# sensors_and_led.net
KiCad netlist of a schematic drawn in Altium Designer
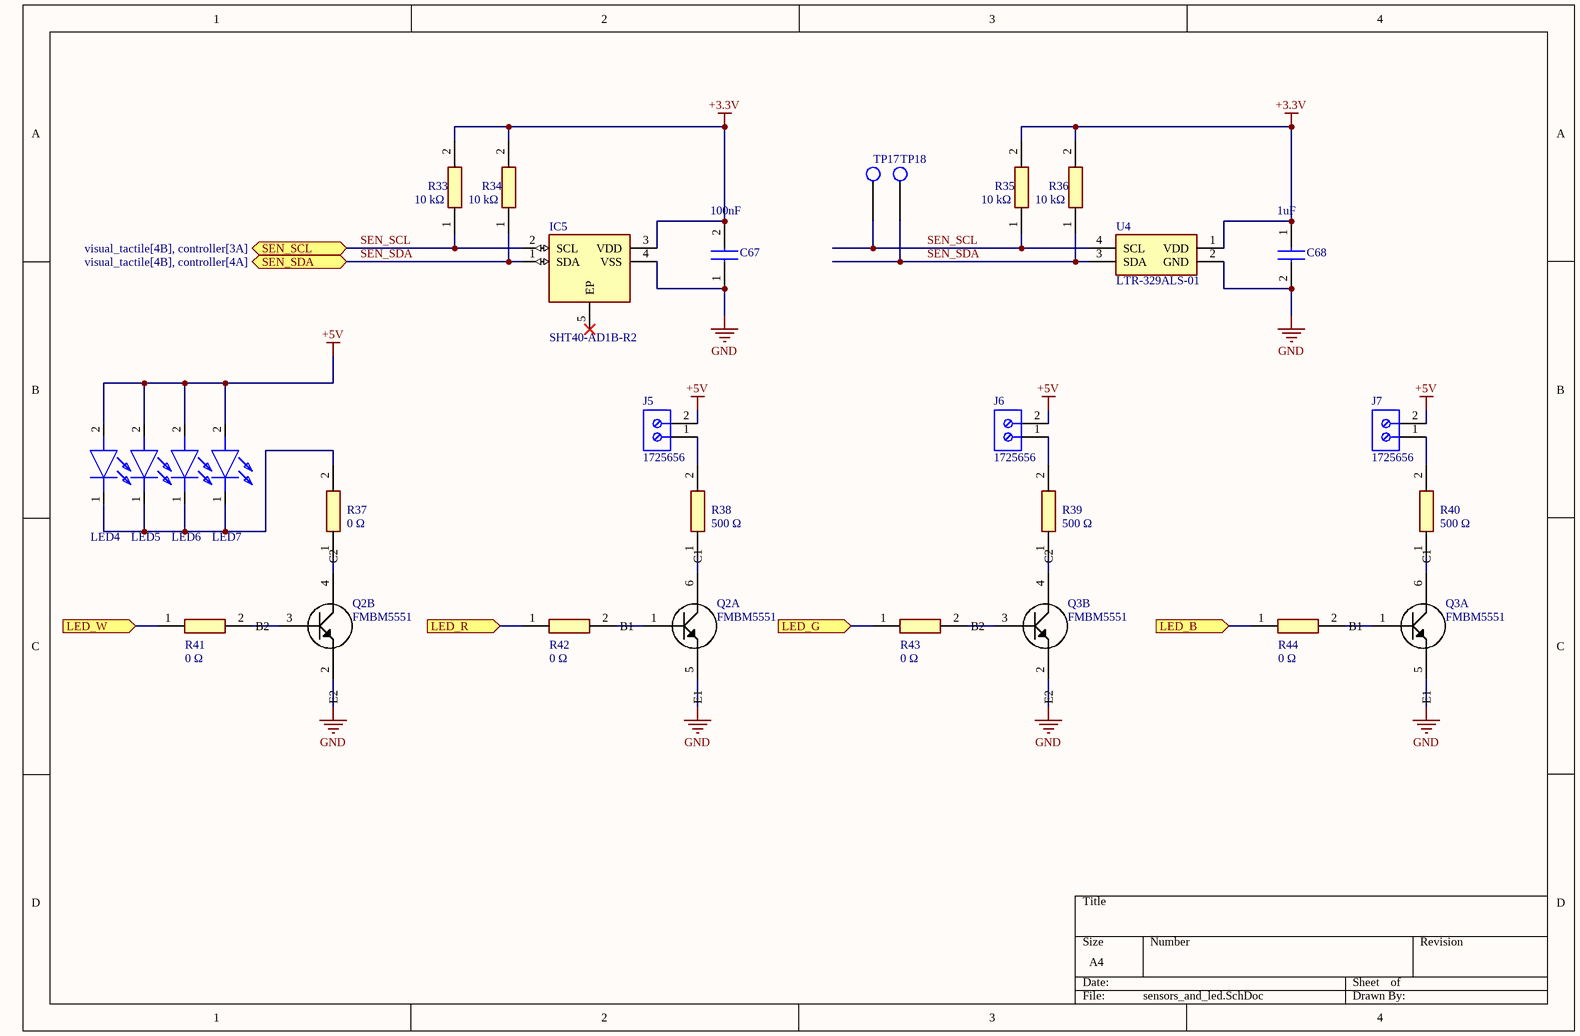
[diagram p0: sensors_and_led.SchDoc]

(export (version "E")
  (design (tool "Eeschema 10.0.6"))
  (components
    (comp (ref "C67")
      (value "100nF")
      (footprint "PCB_library:CAPC1608X87N")
      (fields
        (field (name "MANUFACTURER_PART_NUMBER") "C0603C300J5GACTU")
        (field (name "MOUSER PART NUMBER") "80-C0603C300J5G")
        (field (name "MANUFACTURER") "TDK")
      )
      (libsource (lib "PCB_library") (part "C0603C300J5GACTU"))
    )
    (comp (ref "C68")
      (value "1uF")
      (footprint "PCB_library:CAPC1608X87N")
      (fields
        (field (name "MANUFACTURER_PART_NUMBER") "C0603C300J5GACTU")
        (field (name "MOUSER PART NUMBER") "80-C0603C300J5G")
        (field (name "MANUFACTURER") "Kyocera AVX")
      )
      (libsource (lib "PCB_library") (part "C0603C300J5GACTU"))
    )
    (comp (ref "IC5")
      (value "SHT40-AD1B-R2")
      (footprint "PCB_library:SON80P150X150X59-5N")
      (description "Integrated Circuit")
      (fields (field (name "MOUSER PART NUMBER") "403-SHT40-AD1B-R2"))
      (libsource (lib "PCB_library") (part "SHT40-AD1B-R2"))
    )
    (comp (ref "J5")
      (value "1725656")
      (footprint "PHOE-1725656-2")
      (description "Male Header, Pitch 2.54 mm, 1 x 2 Position, Height 9 mm, Tail Length 3.5 mm")
      (fields (field (name "MANUFACTURER") "Phoenix Contact"))
      (libsource (lib "Altium Content Vault") (part "CN-1P-F-TB2"))
    )
    (comp (ref "J6")
      (value "1725656")
      (footprint "PHOE-1725656-2")
      (description "Male Header, Pitch 2.54 mm, 1 x 2 Position, Height 9 mm, Tail Length 3.5 mm")
      (fields (field (name "MANUFACTURER") "Phoenix Contact"))
      (libsource (lib "Altium Content Vault") (part "CN-1P-F-TB2"))
    )
    (comp (ref "J7")
      (value "1725656")
      (footprint "PHOE-1725656-2")
      (description "Male Header, Pitch 2.54 mm, 1 x 2 Position, Height 9 mm, Tail Length 3.5 mm")
      (fields (field (name "MANUFACTURER") "Phoenix Contact"))
      (libsource (lib "Altium Content Vault") (part "CN-1P-F-TB2"))
    )
    (comp (ref "LED4")
      (value "JE2835BWT-P-U30GA0000-N0000001")
      (footprint "PCB_library:JE2835BWTPU30GA0000N0000001")
      (description "LED")
      (fields
        (field (name "MANUFACTURER_PART_NUMBER") "JE2835BWT-P-U35GA0000-N0000001")
        (field (name "MOUSER PART NUMBER") "941-JE2835BWTPU30GAN")
      )
      (libsource (lib "PCB_library") (part "JE2835BWT-P-U30GA0000-N0000001"))
    )
    (comp (ref "LED5")
      (value "JE2835BWT-P-U30GA0000-N0000001")
      (footprint "PCB_library:JE2835BWTPU30GA0000N0000001")
      (description "LED")
      (fields
        (field (name "MANUFACTURER_PART_NUMBER") "JE2835BWT-P-U35GA0000-N0000001")
        (field (name "MOUSER PART NUMBER") "941-JE2835BWTPU30GAN")
      )
      (libsource (lib "PCB_library") (part "JE2835BWT-P-U30GA0000-N0000001"))
    )
    (comp (ref "LED6")
      (value "JE2835BWT-P-U30GA0000-N0000001")
      (footprint "PCB_library:JE2835BWTPU30GA0000N0000001")
      (description "LED")
      (fields
        (field (name "MANUFACTURER_PART_NUMBER") "JE2835BWT-P-U35GA0000-N0000001")
        (field (name "MOUSER PART NUMBER") "941-JE2835BWTPU30GAN")
      )
      (libsource (lib "PCB_library") (part "JE2835BWT-P-U30GA0000-N0000001"))
    )
    (comp (ref "LED7")
      (value "JE2835BWT-P-U30GA0000-N0000001")
      (footprint "PCB_library:JE2835BWTPU30GA0000N0000001")
      (description "LED")
      (fields
        (field (name "MANUFACTURER_PART_NUMBER") "JE2835BWT-P-U35GA0000-N0000001")
        (field (name "MOUSER PART NUMBER") "941-JE2835BWTPU30GAN")
      )
      (libsource (lib "PCB_library") (part "JE2835BWT-P-U30GA0000-N0000001"))
    )
    (comp (ref "Q2")
      (value "FMBM5551")
      (footprint "PCB_library:SOT95P280X110-6N")
      (description "Transistor NPN/NPN BISS")
      (fields (field (name "MOUSER PART NUMBER") "512-FMBM5551"))
      (libsource (lib "PCB_library") (part "FMBM5551"))
    )
    (comp (ref "Q3")
      (value "FMBM5551")
      (footprint "PCB_library:SOT95P280X110-6N")
      (description "Transistor NPN/NPN BISS")
      (fields (field (name "MOUSER PART NUMBER") "512-FMBM5551"))
      (libsource (lib "PCB_library") (part "FMBM5551"))
    )
    (comp (ref "R33")
      (value "10 kΩ")
      (footprint "RESC1005X35N")
      (description "Resistor")
      (fields
        (field (name "MANUFACTURER_PART_NUMBER") "CPF0402B100KE")
        (field (name "MOUSER PART NUMBER") "279-CPF0402B100KE")
      )
      (libsource (lib "*") (part "CPF0402B100KE"))
    )
    (comp (ref "R34")
      (value "10 kΩ")
      (footprint "RESC1005X35N")
      (description "Resistor")
      (fields
        (field (name "MANUFACTURER_PART_NUMBER") "CPF0402B100KE")
        (field (name "MOUSER PART NUMBER") "279-CPF0402B100KE")
      )
      (libsource (lib "*") (part "CPF0402B100KE"))
    )
    (comp (ref "R35")
      (value "10 kΩ")
      (footprint "RESC1005X35N")
      (description "Resistor")
      (fields
        (field (name "MANUFACTURER_PART_NUMBER") "CPF0402B100KE")
        (field (name "MOUSER PART NUMBER") "279-CPF0402B100KE")
      )
      (libsource (lib "*") (part "CPF0402B100KE"))
    )
    (comp (ref "R36")
      (value "10 kΩ")
      (footprint "RESC1005X35N")
      (description "Resistor")
      (fields
        (field (name "MANUFACTURER_PART_NUMBER") "CPF0402B100KE")
        (field (name "MOUSER PART NUMBER") "279-CPF0402B100KE")
      )
      (libsource (lib "*") (part "CPF0402B100KE"))
    )
    (comp (ref "R37")
      (value "0 Ω")
      (footprint "RESC1005X35N")
      (description "Resistor")
      (fields
        (field (name "MANUFACTURER_PART_NUMBER") "CPF0402B100KE")
        (field (name "MOUSER PART NUMBER") "279-CPF0402B100KE")
      )
      (libsource (lib "*") (part "CPF0402B100KE"))
    )
    (comp (ref "R38")
      (value "500 Ω")
      (footprint "RESC1005X35N")
      (description "Resistor")
      (fields
        (field (name "MANUFACTURER_PART_NUMBER") "CPF0402B100KE")
        (field (name "MOUSER PART NUMBER") "279-CPF0402B100KE")
      )
      (libsource (lib "*") (part "CPF0402B100KE"))
    )
    (comp (ref "R39")
      (value "500 Ω")
      (footprint "RESC1005X35N")
      (description "Resistor")
      (fields
        (field (name "MANUFACTURER_PART_NUMBER") "CPF0402B100KE")
        (field (name "MOUSER PART NUMBER") "279-CPF0402B100KE")
      )
      (libsource (lib "*") (part "CPF0402B100KE"))
    )
    (comp (ref "R40")
      (value "500 Ω")
      (footprint "RESC1005X35N")
      (description "Resistor")
      (fields
        (field (name "MANUFACTURER_PART_NUMBER") "CPF0402B100KE")
        (field (name "MOUSER PART NUMBER") "279-CPF0402B100KE")
      )
      (libsource (lib "*") (part "CPF0402B100KE"))
    )
    (comp (ref "R41")
      (value "0 Ω")
      (footprint "RESC1005X35N")
      (description "Resistor")
      (fields
        (field (name "MANUFACTURER_PART_NUMBER") "CPF0402B100KE")
        (field (name "MOUSER PART NUMBER") "279-CPF0402B100KE")
      )
      (libsource (lib "") (part "CPF0402B100KE_1"))
    )
    (comp (ref "R42")
      (value "0 Ω")
      (footprint "RESC1005X35N")
      (description "Resistor")
      (fields
        (field (name "MANUFACTURER_PART_NUMBER") "CPF0402B100KE")
        (field (name "MOUSER PART NUMBER") "279-CPF0402B100KE")
      )
      (libsource (lib "") (part "CPF0402B100KE_1"))
    )
    (comp (ref "R43")
      (value "0 Ω")
      (footprint "RESC1005X35N")
      (description "Resistor")
      (fields
        (field (name "MANUFACTURER_PART_NUMBER") "CPF0402B100KE")
        (field (name "MOUSER PART NUMBER") "279-CPF0402B100KE")
      )
      (libsource (lib "") (part "CPF0402B100KE_1"))
    )
    (comp (ref "R44")
      (value "0 Ω")
      (footprint "RESC1005X35N")
      (description "Resistor")
      (fields
        (field (name "MANUFACTURER_PART_NUMBER") "CPF0402B100KE")
        (field (name "MOUSER PART NUMBER") "279-CPF0402B100KE")
      )
      (libsource (lib "") (part "CPF0402B100KE_1"))
    )
    (comp (ref "TP17")
      (value "Test point")
      (footprint "test point")
      (libsource (lib "PCB_library") (part "Test point"))
    )
    (comp (ref "TP18")
      (value "Test point")
      (footprint "test point")
      (libsource (lib "PCB_library") (part "Test point"))
    )
    (comp (ref "U4")
      (value "LTR-329ALS-01")
      (footprint "PCB_library:LTR329ALS01")
      (description "Undefined or Miscellaneous")
      (fields (field (name "MOUSER PART NUMBER") "859-LTR-329ALS-01"))
      (libsource (lib "PCB_library") (part "LTR-329ALS-01"))
    )
  )
  (nets
    (net (code "1") (name "+3.3V") (class "Default")
      (node (ref "C67") (pin "2") (pinfunction "2_2") (pintype "passive"))
      (node (ref "C68") (pin "1") (pinfunction "1_1") (pintype "passive"))
      (node (ref "IC5") (pin "3") (pinfunction "VDD_3") (pintype "power_in"))
      (node (ref "R33") (pin "2") (pinfunction "2_2") (pintype "passive"))
      (node (ref "R34") (pin "2") (pinfunction "2_2") (pintype "passive"))
      (node (ref "R35") (pin "2") (pinfunction "2_2") (pintype "passive"))
      (node (ref "R36") (pin "2") (pinfunction "2_2") (pintype "passive"))
      (node (ref "U4") (pin "1") (pinfunction "VDD_1") (pintype "passive"))
    )
    (net (code "2") (name "+5V") (class "Default")
      (node (ref "J5") (pin "2") (pinfunction "2_2") (pintype "passive"))
      (node (ref "J6") (pin "2") (pinfunction "2_2") (pintype "passive"))
      (node (ref "J7") (pin "2") (pinfunction "2_2") (pintype "passive"))
      (node (ref "LED4") (pin "2") (pinfunction "A_2") (pintype "passive"))
      (node (ref "LED5") (pin "2") (pinfunction "A_2") (pintype "passive"))
      (node (ref "LED6") (pin "2") (pinfunction "A_2") (pintype "passive"))
      (node (ref "LED7") (pin "2") (pinfunction "A_2") (pintype "passive"))
    )
    (net (code "3") (name "/LED_B") (class "Default")
      (node (ref "R44") (pin "1") (pinfunction "1_1") (pintype "passive"))
    )
    (net (code "4") (name "/LED_G") (class "Default")
      (node (ref "R43") (pin "1") (pinfunction "1_1") (pintype "passive"))
    )
    (net (code "5") (name "/LED_R") (class "Default")
      (node (ref "R42") (pin "1") (pinfunction "1_1") (pintype "passive"))
    )
    (net (code "6") (name "/LED_W") (class "Default")
      (node (ref "R41") (pin "1") (pinfunction "1_1") (pintype "passive"))
    )
    (net (code "7") (name "/SEN_SCL") (class "Default")
      (node (ref "IC5") (pin "2") (pinfunction "SCL_2") (pintype "bidirectional"))
      (node (ref "R33") (pin "1") (pinfunction "1_1") (pintype "passive"))
      (node (ref "R35") (pin "1") (pinfunction "1_1") (pintype "passive"))
      (node (ref "TP17") (pin "1") (pinfunction "1_1") (pintype "passive"))
      (node (ref "U4") (pin "4") (pinfunction "SCL_4") (pintype "passive"))
    )
    (net (code "8") (name "/SEN_SDA") (class "Default")
      (node (ref "IC5") (pin "1") (pinfunction "SDA_1") (pintype "bidirectional"))
      (node (ref "R34") (pin "1") (pinfunction "1_1") (pintype "passive"))
      (node (ref "R36") (pin "1") (pinfunction "1_1") (pintype "passive"))
      (node (ref "TP18") (pin "1") (pinfunction "1_1") (pintype "passive"))
      (node (ref "U4") (pin "3") (pinfunction "SDA_3") (pintype "passive"))
    )
    (net (code "9") (name "GND") (class "Default")
      (node (ref "C67") (pin "1") (pinfunction "1_1") (pintype "passive"))
      (node (ref "C68") (pin "2") (pinfunction "2_2") (pintype "passive"))
      (node (ref "IC5") (pin "4") (pinfunction "VSS_4") (pintype "power_in"))
      (node (ref "Q2") (pin "2") (pinfunction "E2_2") (pintype "passive"))
      (node (ref "Q2") (pin "5") (pinfunction "E1_5") (pintype "passive"))
      (node (ref "Q3") (pin "2") (pinfunction "E2_2") (pintype "passive"))
      (node (ref "Q3") (pin "5") (pinfunction "E1_5") (pintype "passive"))
      (node (ref "U4") (pin "2") (pinfunction "GND_2") (pintype "passive"))
    )
    (net (code "10") (name "Net-(J5-Pad1)") (class "Default")
      (node (ref "J5") (pin "1") (pinfunction "1_1") (pintype "passive"))
      (node (ref "R38") (pin "2") (pinfunction "2_2") (pintype "passive"))
    )
    (net (code "11") (name "Net-(J6-Pad1)") (class "Default")
      (node (ref "J6") (pin "1") (pinfunction "1_1") (pintype "passive"))
      (node (ref "R39") (pin "2") (pinfunction "2_2") (pintype "passive"))
    )
    (net (code "12") (name "Net-(J7-Pad1)") (class "Default")
      (node (ref "J7") (pin "1") (pinfunction "1_1") (pintype "passive"))
      (node (ref "R40") (pin "2") (pinfunction "2_2") (pintype "passive"))
    )
    (net (code "13") (name "Net-(LED4A-K)") (class "Default")
      (node (ref "LED4") (pin "1") (pinfunction "K_1") (pintype "passive"))
      (node (ref "LED5") (pin "1") (pinfunction "K_1") (pintype "passive"))
      (node (ref "LED6") (pin "1") (pinfunction "K_1") (pintype "passive"))
      (node (ref "LED7") (pin "1") (pinfunction "K_1") (pintype "passive"))
      (node (ref "R37") (pin "2") (pinfunction "2_2") (pintype "passive"))
    )
    (net (code "14") (name "Net-(Q2A-B1)") (class "Default")
      (node (ref "Q2") (pin "1") (pinfunction "B1_1") (pintype "passive"))
      (node (ref "R42") (pin "2") (pinfunction "2_2") (pintype "passive"))
    )
    (net (code "15") (name "Net-(Q2A-C1)") (class "Default")
      (node (ref "Q2") (pin "6") (pinfunction "C1_6") (pintype "passive"))
      (node (ref "R38") (pin "1") (pinfunction "1_1") (pintype "passive"))
    )
    (net (code "16") (name "Net-(Q2B-B2)") (class "Default")
      (node (ref "Q2") (pin "3") (pinfunction "B2_3") (pintype "passive"))
      (node (ref "R41") (pin "2") (pinfunction "2_2") (pintype "passive"))
    )
    (net (code "17") (name "Net-(Q2B-C2)") (class "Default")
      (node (ref "Q2") (pin "4") (pinfunction "C2_4") (pintype "passive"))
      (node (ref "R37") (pin "1") (pinfunction "1_1") (pintype "passive"))
    )
    (net (code "18") (name "Net-(Q3A-B1)") (class "Default")
      (node (ref "Q3") (pin "1") (pinfunction "B1_1") (pintype "passive"))
      (node (ref "R44") (pin "2") (pinfunction "2_2") (pintype "passive"))
    )
    (net (code "19") (name "Net-(Q3A-C1)") (class "Default")
      (node (ref "Q3") (pin "6") (pinfunction "C1_6") (pintype "passive"))
      (node (ref "R40") (pin "1") (pinfunction "1_1") (pintype "passive"))
    )
    (net (code "20") (name "Net-(Q3B-B2)") (class "Default")
      (node (ref "Q3") (pin "3") (pinfunction "B2_3") (pintype "passive"))
      (node (ref "R43") (pin "2") (pinfunction "2_2") (pintype "passive"))
    )
    (net (code "21") (name "Net-(Q3B-C2)") (class "Default")
      (node (ref "Q3") (pin "4") (pinfunction "C2_4") (pintype "passive"))
      (node (ref "R39") (pin "1") (pinfunction "1_1") (pintype "passive"))
    )
    (net (code "22") (name "unconnected-(IC5-EP-Pad5)") (class "Default")
      (node (ref "IC5") (pin "5") (pinfunction "EP_5") (pintype "power_in+no_connect"))
    )
  )
)
